# Sheet1.net
KiCad netlist of a schematic drawn in Altium Designer
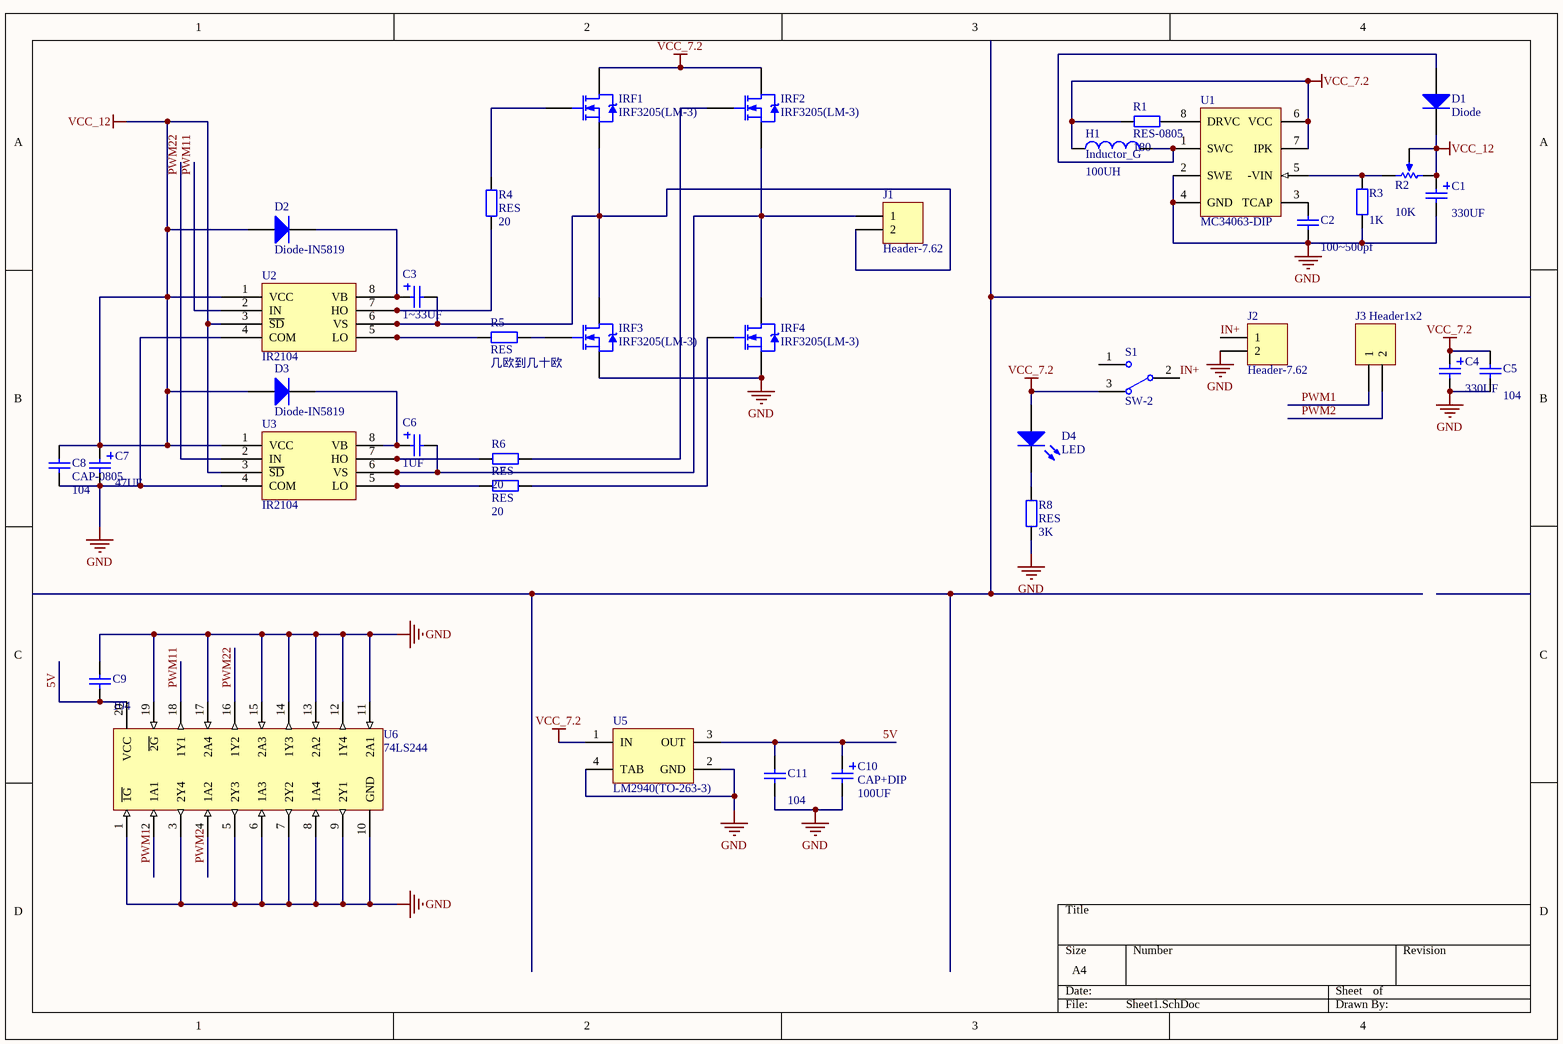
[diagram p0: Sheet1.SchDoc]

(export (version "E")
  (design (tool "Eeschema 10.0.6"))
  (components
    (comp (ref "C1")
      (value "CAP+DIP")
      (footprint "CAP+DIP")
      (fields (field (name "ALTIUM_UNNAMED_1") "330UF"))
      (libsource (lib "LXK_Common") (part "CAP+DIP"))
    )
    (comp (ref "C2")
      (value "CAP-0805")
      (footprint "CAP-0805")
      (fields (field (name "ALTIUM_UNNAMED_1") "100~500pf"))
      (libsource (lib "ZYF_Common") (part "CAP-0805"))
    )
    (comp (ref "C3")
      (value "CAP+DIP")
      (footprint "CAP+DIP")
      (fields (field (name "ALTIUM_UNNAMED_1") "1~33UF"))
      (libsource (lib "LXK_Common") (part "CAP+DIP"))
    )
    (comp (ref "C4")
      (value "CAP+DIP")
      (footprint "CAP+DIP")
      (fields (field (name "ALTIUM_UNNAMED_1") "330UF"))
      (libsource (lib "LXK_Common") (part "CAP+DIP"))
    )
    (comp (ref "C5")
      (value "CAP-0805")
      (footprint "CAP-0805")
      (fields (field (name "ALTIUM_UNNAMED_1") "104"))
      (libsource (lib "ZYF_Common") (part "CAP-0805"))
    )
    (comp (ref "C6")
      (value "CAP+DIP")
      (footprint "CAP+DIP")
      (fields (field (name "ALTIUM_UNNAMED_1") "1UF"))
      (libsource (lib "LXK_Common") (part "CAP+DIP"))
    )
    (comp (ref "C7")
      (value "CAP+DIP")
      (footprint "CAP+DIP")
      (fields (field (name "ALTIUM_UNNAMED_1") "47UF"))
      (libsource (lib "LXK_Common") (part "CAP+DIP"))
    )
    (comp (ref "C8")
      (value "CAP-0805")
      (footprint "CAP-0805")
      (fields (field (name "ALTIUM_UNNAMED_1") "104"))
      (libsource (lib "ZYF_Common") (part "CAP-0805"))
    )
    (comp (ref "C9")
      (value "CAP-0805")
      (footprint "CAP-0805")
      (fields (field (name "ALTIUM_UNNAMED_1") "104"))
      (libsource (lib "ZYF_Common") (part "CAP-0805"))
    )
    (comp (ref "C10")
      (value "CAP+DIP")
      (footprint "CAP+DIP")
      (fields (field (name "ALTIUM_UNNAMED_1") "100UF"))
      (libsource (lib "LXK_Common") (part "CAP+DIP"))
    )
    (comp (ref "C11")
      (value "CAP-0805")
      (footprint "CAP-0805")
      (fields (field (name "ALTIUM_UNNAMED_1") "104"))
      (libsource (lib "ZYF_Common") (part "CAP-0805"))
    )
    (comp (ref "D1") (value "Diode") (footprint "DIODE-DIP") (libsource (lib "LXK_Common") (part "Diode")))
    (comp (ref "D2")
      (value "Diode-IN5819")
      (footprint "Diode-IN5819")
      (libsource (lib "ZYF_Common") (part "Diode-IN5819"))
    )
    (comp (ref "D3")
      (value "Diode-IN5819")
      (footprint "Diode-IN5819")
      (libsource (lib "ZYF_Common") (part "Diode-IN5819"))
    )
    (comp (ref "D4") (value "LED") (footprint "LED") (libsource (lib "LXK_Common") (part "LED")))
    (comp (ref "H1")
      (value "Inductor_G")
      (footprint "INDUCTOR-G")
      (fields (field (name "ALTIUM_UNNAMED_1") "100UH"))
      (libsource (lib "LXK_Common") (part "Inductor_G"))
    )
    (comp (ref "IRF1")
      (value "IRF3205(LM-3)")
      (footprint "LM-3")
      (libsource (lib "ZYF_IC") (part "IRF3205(LM-3)"))
    )
    (comp (ref "IRF2")
      (value "IRF3205(LM-3)")
      (footprint "LM-3")
      (libsource (lib "ZYF_IC") (part "IRF3205(LM-3)"))
    )
    (comp (ref "IRF3")
      (value "IRF3205(LM-3)")
      (footprint "LM-3")
      (libsource (lib "ZYF_IC") (part "IRF3205(LM-3)"))
    )
    (comp (ref "IRF4")
      (value "IRF3205(LM-3)")
      (footprint "LM-3")
      (libsource (lib "ZYF_IC") (part "IRF3205(LM-3)"))
    )
    (comp (ref "J1")
      (value "Header-7.62")
      (footprint "HEADER-7.5")
      (libsource (lib "LXK_Connector") (part "Header-7.62"))
    )
    (comp (ref "J2")
      (value "Header-7.62")
      (footprint "HEADER-7.5")
      (libsource (lib "ZYF_Connector") (part "Header-7.62"))
    )
    (comp (ref "J3")
      (value "Header1x2")
      (footprint "HEADER1X2")
      (libsource (lib "ZYF_Connector") (part "Header1x2"))
    )
    (comp (ref "R1")
      (value "RES-0805")
      (footprint "RES-0805")
      (fields (field (name "ALTIUM_UNNAMED_1") "180"))
      (libsource (lib "ZYF_Common") (part "RES-0805"))
    )
    (comp (ref "R2")
      (value "RES-Change")
      (footprint "RES-Change")
      (fields (field (name "ALTIUM_UNNAMED_1") "10K"))
      (libsource (lib "ZYF_Common") (part "RES-Change"))
    )
    (comp (ref "R3")
      (value "RES-0805")
      (footprint "RES-0805")
      (fields (field (name "ALTIUM_UNNAMED_1") "1K"))
      (libsource (lib "ZYF_Common") (part "RES-0805"))
    )
    (comp (ref "R4")
      (value "RES")
      (footprint "RES")
      (fields (field (name "ALTIUM_UNNAMED_1") "20"))
      (libsource (lib "LXK_Common") (part "RES"))
    )
    (comp (ref "R5")
      (value "RES")
      (footprint "RES")
      (fields (field (name "ALTIUM_UNNAMED_1") "几欧到几十欧"))
      (libsource (lib "LXK_Common") (part "RES"))
    )
    (comp (ref "R6")
      (value "RES")
      (footprint "RES")
      (fields (field (name "ALTIUM_UNNAMED_1") "20"))
      (libsource (lib "LXK_Common") (part "RES"))
    )
    (comp (ref "R7")
      (value "RES")
      (footprint "RES")
      (fields (field (name "ALTIUM_UNNAMED_1") "20"))
      (libsource (lib "LXK_Common") (part "RES"))
    )
    (comp (ref "R8")
      (value "RES")
      (footprint "RES")
      (fields (field (name "ALTIUM_UNNAMED_1") "3K"))
      (libsource (lib "LXK_Common") (part "RES"))
    )
    (comp (ref "S1") (value "SW-2") (footprint "SW-2") (libsource (lib "LXK_Common") (part "SW-2")))
    (comp (ref "U1")
      (value "MC34063-DIP")
      (footprint "DIP-8")
      (libsource (lib "ZYF_IC") (part "MC34063-DIP"))
    )
    (comp (ref "U2") (value "IR2104") (footprint "SOP-8") (libsource (lib "ZYF_IC") (part "IR2104")))
    (comp (ref "U3") (value "IR2104") (footprint "SOP-8") (libsource (lib "ZYF_IC") (part "IR2104")))
    (comp (ref "U5")
      (value "LM2940(TO-263-3)")
      (footprint "TO-263-3")
      (libsource (lib "ZYF_IC") (part "LM2940(TO-263-3)"))
    )
    (comp (ref "U6") (value "74LS244") (footprint "DIP-20") (libsource (lib "ZYF_IC") (part "74LS244")))
  )
  (nets
    (net (code "1") (name "/5V") (class "Default")
      (node (ref "C10") (pin "1") (pinfunction "1_1") (pintype "passive"))
      (node (ref "C11") (pin "2") (pinfunction "2_2") (pintype "passive"))
      (node (ref "C9") (pin "1") (pinfunction "1_1") (pintype "passive"))
      (node (ref "U5") (pin "3") (pinfunction "OUT_3") (pintype "power_in"))
      (node (ref "U6") (pin "20") (pinfunction "VCC_20") (pintype "power_in"))
    )
    (net (code "2") (name "/IN+") (class "Default")
      (node (ref "J2") (pin "1") (pinfunction "1_1") (pintype "passive"))
      (node (ref "S1") (pin "2") (pinfunction "2_2") (pintype "passive"))
    )
    (net (code "3") (name "/PWM1") (class "Default")
      (node (ref "J3") (pin "1") (pinfunction "1_1") (pintype "passive"))
      (node (ref "U6") (pin "2") (pinfunction "1A1_2") (pintype "input"))
    )
    (net (code "4") (name "/PWM2") (class "Default")
      (node (ref "J3") (pin "2") (pinfunction "2_2") (pintype "passive"))
      (node (ref "U6") (pin "4") (pinfunction "1A2_4") (pintype "input"))
    )
    (net (code "5") (name "/PWM11") (class "Default")
      (node (ref "U2") (pin "2") (pinfunction "IN_2") (pintype "passive"))
      (node (ref "U6") (pin "18") (pinfunction "1Y1_18") (pintype "output"))
    )
    (net (code "6") (name "/PWM22") (class "Default")
      (node (ref "U3") (pin "2") (pinfunction "IN_2") (pintype "passive"))
      (node (ref "U6") (pin "16") (pinfunction "1Y2_16") (pintype "output"))
    )
    (net (code "7") (name "GND") (class "Default")
      (node (ref "C1") (pin "2") (pinfunction "2_2") (pintype "passive"))
      (node (ref "C10") (pin "2") (pinfunction "2_2") (pintype "passive"))
      (node (ref "C11") (pin "1") (pinfunction "1_1") (pintype "passive"))
      (node (ref "C2") (pin "1") (pinfunction "1_1") (pintype "passive"))
      (node (ref "C4") (pin "2") (pinfunction "2_2") (pintype "passive"))
      (node (ref "C5") (pin "1") (pinfunction "1_1") (pintype "passive"))
      (node (ref "C7") (pin "2") (pinfunction "2_2") (pintype "passive"))
      (node (ref "C8") (pin "1") (pinfunction "1_1") (pintype "passive"))
      (node (ref "C9") (pin "2") (pinfunction "2_2") (pintype "passive"))
      (node (ref "IRF3") (pin "3") (pinfunction "S_3") (pintype "passive"))
      (node (ref "IRF4") (pin "3") (pinfunction "S_3") (pintype "passive"))
      (node (ref "J2") (pin "2") (pinfunction "2_2") (pintype "passive"))
      (node (ref "R3") (pin "1") (pinfunction "1_1") (pintype "passive"))
      (node (ref "R8") (pin "2") (pinfunction "2_2") (pintype "passive"))
      (node (ref "U1") (pin "2") (pinfunction "SWE_2") (pintype "open_emitter"))
      (node (ref "U1") (pin "4") (pinfunction "GND_4") (pintype "power_in"))
      (node (ref "U2") (pin "4") (pinfunction "COM_4") (pintype "passive"))
      (node (ref "U3") (pin "4") (pinfunction "COM_4") (pintype "passive"))
      (node (ref "U5") (pin "2") (pinfunction "GND_2") (pintype "power_in"))
      (node (ref "U5") (pin "4") (pinfunction "TAB_4") (pintype "power_in"))
      (node (ref "U6") (pin "1") (pinfunction "~{1G}_1") (pintype "input"))
      (node (ref "U6") (pin "10") (pinfunction "GND_10") (pintype "power_in"))
      (node (ref "U6") (pin "11") (pinfunction "2A1_11") (pintype "input"))
      (node (ref "U6") (pin "12") (pinfunction "1Y4_12") (pintype "output"))
      (node (ref "U6") (pin "13") (pinfunction "2A2_13") (pintype "input"))
      (node (ref "U6") (pin "14") (pinfunction "1Y3_14") (pintype "output"))
      (node (ref "U6") (pin "15") (pinfunction "2A3_15") (pintype "input"))
      (node (ref "U6") (pin "17") (pinfunction "2A4_17") (pintype "input"))
      (node (ref "U6") (pin "19") (pinfunction "~{2G}_19") (pintype "input"))
      (node (ref "U6") (pin "3") (pinfunction "2Y4_3") (pintype "output"))
      (node (ref "U6") (pin "5") (pinfunction "2Y3_5") (pintype "output"))
      (node (ref "U6") (pin "6") (pinfunction "1A3_6") (pintype "input"))
      (node (ref "U6") (pin "7") (pinfunction "2Y2_7") (pintype "output"))
      (node (ref "U6") (pin "8") (pinfunction "1A4_8") (pintype "input"))
      (node (ref "U6") (pin "9") (pinfunction "2Y1_9") (pintype "output"))
    )
    (net (code "8") (name "Net-(D1-A)") (class "Default")
      (node (ref "D1") (pin "1") (pinfunction "A_1") (pintype "passive"))
      (node (ref "H1") (pin "2") (pinfunction "2_2") (pintype "passive"))
      (node (ref "U1") (pin "1") (pinfunction "SWC_1") (pintype "open_collector"))
    )
    (net (code "9") (name "Net-(D2-K)") (class "Default")
      (node (ref "C3") (pin "1") (pinfunction "1_1") (pintype "passive"))
      (node (ref "D2") (pin "2") (pinfunction "K_2") (pintype "passive"))
      (node (ref "U2") (pin "8") (pinfunction "VB_8") (pintype "passive"))
    )
    (net (code "10") (name "Net-(D3-K)") (class "Default")
      (node (ref "C6") (pin "1") (pinfunction "1_1") (pintype "passive"))
      (node (ref "D3") (pin "2") (pinfunction "K_2") (pintype "passive"))
      (node (ref "U3") (pin "8") (pinfunction "VB_8") (pintype "passive"))
    )
    (net (code "11") (name "Net-(D4-K)") (class "Default")
      (node (ref "D4") (pin "2") (pinfunction "K_2") (pintype "passive"))
      (node (ref "R8") (pin "1") (pinfunction "1_1") (pintype "passive"))
    )
    (net (code "12") (name "Net-(IRF1-G)") (class "Default")
      (node (ref "IRF1") (pin "1") (pinfunction "G_1") (pintype "passive"))
      (node (ref "R4") (pin "2") (pinfunction "2_2") (pintype "passive"))
    )
    (net (code "13") (name "Net-(IRF1-S)") (class "Default")
      (node (ref "C3") (pin "2") (pinfunction "2_2") (pintype "passive"))
      (node (ref "IRF1") (pin "3") (pinfunction "S_3") (pintype "passive"))
      (node (ref "IRF3") (pin "2") (pinfunction "D_2") (pintype "passive"))
      (node (ref "J1") (pin "2") (pinfunction "2_2") (pintype "passive"))
      (node (ref "U2") (pin "6") (pinfunction "VS_6") (pintype "passive"))
    )
    (net (code "14") (name "Net-(IRF2-G)") (class "Default")
      (node (ref "IRF2") (pin "1") (pinfunction "G_1") (pintype "passive"))
      (node (ref "R6") (pin "2") (pinfunction "2_2") (pintype "passive"))
    )
    (net (code "15") (name "Net-(IRF2-S)") (class "Default")
      (node (ref "C6") (pin "2") (pinfunction "2_2") (pintype "passive"))
      (node (ref "IRF2") (pin "3") (pinfunction "S_3") (pintype "passive"))
      (node (ref "IRF4") (pin "2") (pinfunction "D_2") (pintype "passive"))
      (node (ref "J1") (pin "1") (pinfunction "1_1") (pintype "passive"))
      (node (ref "U3") (pin "6") (pinfunction "VS_6") (pintype "passive"))
    )
    (net (code "16") (name "Net-(IRF3-G)") (class "Default")
      (node (ref "IRF3") (pin "1") (pinfunction "G_1") (pintype "passive"))
      (node (ref "R5") (pin "1") (pinfunction "1_1") (pintype "passive"))
    )
    (net (code "17") (name "Net-(IRF4-G)") (class "Default")
      (node (ref "IRF4") (pin "1") (pinfunction "G_1") (pintype "passive"))
      (node (ref "R7") (pin "1") (pinfunction "1_1") (pintype "passive"))
    )
    (net (code "18") (name "Net-(R2-BOT)") (class "Default")
      (node (ref "R2") (pin "2") (pinfunction "BOT_2") (pintype "passive"))
      (node (ref "R3") (pin "2") (pinfunction "2_2") (pintype "passive"))
      (node (ref "U1") (pin "5") (pinfunction "-VIN_5") (pintype "input"))
    )
    (net (code "19") (name "Net-(U1-DRVC)") (class "Default")
      (node (ref "R1") (pin "2") (pinfunction "2_2") (pintype "passive"))
      (node (ref "U1") (pin "8") (pinfunction "DRVC_8") (pintype "open_collector"))
    )
    (net (code "20") (name "Net-(U1-TCAP)") (class "Default")
      (node (ref "C2") (pin "2") (pinfunction "2_2") (pintype "passive"))
      (node (ref "U1") (pin "3") (pinfunction "TCAP_3") (pintype "passive"))
    )
    (net (code "21") (name "Net-(U2-HO)") (class "Default")
      (node (ref "R4") (pin "1") (pinfunction "1_1") (pintype "passive"))
      (node (ref "U2") (pin "7") (pinfunction "HO_7") (pintype "passive"))
    )
    (net (code "22") (name "Net-(U2-LO)") (class "Default")
      (node (ref "R5") (pin "2") (pinfunction "2_2") (pintype "passive"))
      (node (ref "U2") (pin "5") (pinfunction "LO_5") (pintype "passive"))
    )
    (net (code "23") (name "Net-(U3-HO)") (class "Default")
      (node (ref "R6") (pin "1") (pinfunction "1_1") (pintype "passive"))
      (node (ref "U3") (pin "7") (pinfunction "HO_7") (pintype "passive"))
    )
    (net (code "24") (name "Net-(U3-LO)") (class "Default")
      (node (ref "R7") (pin "2") (pinfunction "2_2") (pintype "passive"))
      (node (ref "U3") (pin "5") (pinfunction "LO_5") (pintype "passive"))
    )
    (net (code "25") (name "VCC_7.2") (class "Default")
      (node (ref "C4") (pin "1") (pinfunction "1_1") (pintype "passive"))
      (node (ref "C5") (pin "2") (pinfunction "2_2") (pintype "passive"))
      (node (ref "D4") (pin "1") (pinfunction "A_1") (pintype "passive"))
      (node (ref "H1") (pin "1") (pinfunction "1_1") (pintype "passive"))
      (node (ref "IRF1") (pin "2") (pinfunction "D_2") (pintype "passive"))
      (node (ref "IRF2") (pin "2") (pinfunction "D_2") (pintype "passive"))
      (node (ref "R1") (pin "1") (pinfunction "1_1") (pintype "passive"))
      (node (ref "S1") (pin "3") (pinfunction "3_3") (pintype "passive"))
      (node (ref "U1") (pin "6") (pinfunction "VCC_6") (pintype "power_in"))
      (node (ref "U1") (pin "7") (pinfunction "IPK_7") (pintype "passive"))
      (node (ref "U5") (pin "1") (pinfunction "IN_1") (pintype "power_in"))
    )
    (net (code "26") (name "VCC_12") (class "Default")
      (node (ref "C1") (pin "1") (pinfunction "1_1") (pintype "passive"))
      (node (ref "C7") (pin "1") (pinfunction "1_1") (pintype "passive"))
      (node (ref "C8") (pin "2") (pinfunction "2_2") (pintype "passive"))
      (node (ref "D1") (pin "2") (pinfunction "K_2") (pintype "passive"))
      (node (ref "D2") (pin "1") (pinfunction "A_1") (pintype "passive"))
      (node (ref "D3") (pin "1") (pinfunction "A_1") (pintype "passive"))
      (node (ref "R2") (pin "1") (pinfunction "TOP_1") (pintype "passive"))
      (node (ref "R2") (pin "3") (pinfunction "TAP_3") (pintype "passive"))
      (node (ref "U2") (pin "1") (pinfunction "VCC_1") (pintype "passive"))
      (node (ref "U2") (pin "3") (pinfunction "~{SD}_3") (pintype "passive"))
      (node (ref "U3") (pin "1") (pinfunction "VCC_1") (pintype "passive"))
      (node (ref "U3") (pin "3") (pinfunction "~{SD}_3") (pintype "passive"))
    )
    (net (code "27") (name "unconnected-(S1-Pad1)") (class "Default")
      (node (ref "S1") (pin "1") (pinfunction "1_1") (pintype "passive"))
    )
  )
)
